# Magnetic_Encoder.net
KiCad netlist of a schematic drawn in Altium Designer
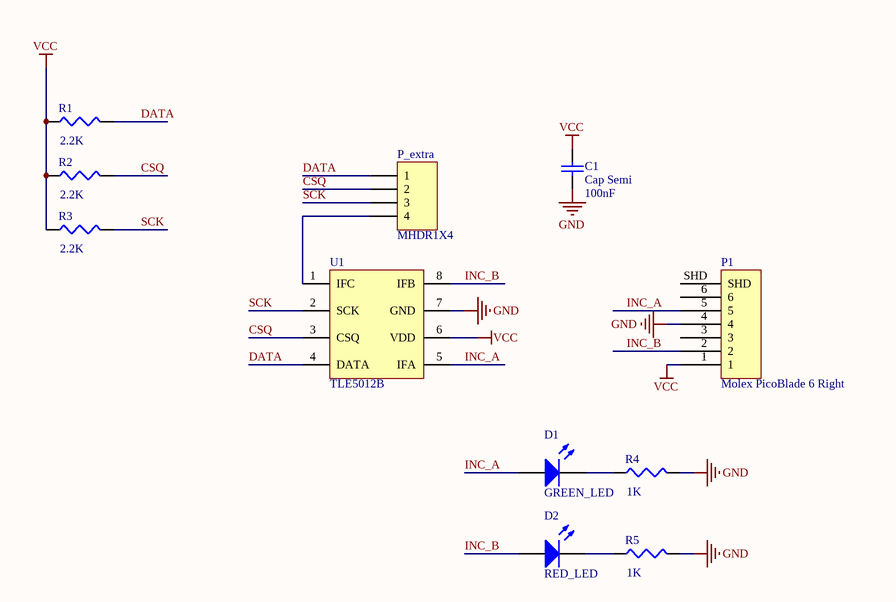
[diagram p0: Magnetic_Encoder.SchDoc]

(export (version "E")
  (design (tool "Eeschema 10.0.6"))
  (components
    (comp (ref "C1")
      (value "Cap Semi")
      (footprint "1608[0603]")
      (description "Capacitor (Semiconductor SIM Model)")
      (fields (field (name "ALTIUM_VALUE") "100nF") (field (name "PUBLISHER") "Altium Limited"))
      (libsource (lib "Miscellaneous Devices") (part "Cap Semi"))
    )
    (comp (ref "D1")
      (value "GREEN_LED")
      (footprint "1608[0603]")
      (description "Typical RED, GREEN, YELLOW, AMBER GaAs LED")
      (fields (field (name "PUBLISHER") "Altium Limited"))
      (libsource (lib "Miscellaneous Devices") (part "LED2"))
    )
    (comp (ref "D2")
      (value "RED_LED")
      (footprint "1608[0603]")
      (description "Typical RED, GREEN, YELLOW, AMBER GaAs LED")
      (fields (field (name "PUBLISHER") "Altium Limited"))
      (libsource (lib "Miscellaneous Devices") (part "LED2"))
    )
    (comp (ref "P1")
      (value "Molex PicoBlade 6 Right")
      (footprint "Molex PicoBlade 6 Right SMD")
      (libsource (lib "ImmPCB2") (part "Molex PicoBlade 6 Right"))
    )
    (comp (ref "P_extra")
      (value "MHDR1X4")
      (footprint "MHDR1X4")
      (description "Header, 4-Pin")
      (fields (field (name "PUBLISHER") "Altium Limited"))
      (libsource (lib "Miscellaneous Connectors") (part "MHDR1X4"))
    )
    (comp (ref "R1")
      (value "2.2K")
      (footprint "J1-0603")
      (description "Resistor")
      (fields (field (name "Comment") "Res3") (field (name "PUBLISHER") "Altium Limited"))
      (libsource (lib "Miscellaneous Devices") (part "Res3"))
    )
    (comp (ref "R2")
      (value "2.2K")
      (footprint "J1-0603")
      (description "Resistor")
      (fields (field (name "Comment") "Res3") (field (name "PUBLISHER") "Altium Limited"))
      (libsource (lib "Miscellaneous Devices") (part "Res3"))
    )
    (comp (ref "R3")
      (value "2.2K")
      (footprint "J1-0603")
      (description "Resistor")
      (fields (field (name "Comment") "Res3") (field (name "PUBLISHER") "Altium Limited"))
      (libsource (lib "Miscellaneous Devices") (part "Res3"))
    )
    (comp (ref "R4")
      (value "1K")
      (footprint "J1-0603")
      (description "Resistor")
      (fields (field (name "Comment") "Res3") (field (name "PUBLISHER") "Altium Limited"))
      (libsource (lib "Miscellaneous Devices") (part "Res3"))
    )
    (comp (ref "R5")
      (value "1K")
      (footprint "J1-0603")
      (description "Resistor")
      (fields (field (name "Comment") "Res3") (field (name "PUBLISHER") "Altium Limited"))
      (libsource (lib "Miscellaneous Devices") (part "Res3"))
    )
    (comp (ref "U1")
      (value "TLE5012B")
      (footprint "SO-8")
      (description "TLE5012BE1000XUMA1")
      (libsource (lib "MagneticEncoder") (part "TLE5012B"))
    )
  )
  (nets
    (net (code "1") (name "/CSQ") (class "Default")
      (node (ref "P_extra") (pin "2") (pinfunction "2_2") (pintype "passive"))
      (node (ref "R2") (pin "2") (pinfunction "2_2") (pintype "passive"))
      (node (ref "U1") (pin "3") (pinfunction "CSQ_3") (pintype "passive"))
    )
    (net (code "2") (name "/DATA") (class "Default")
      (node (ref "P_extra") (pin "1") (pinfunction "1_1") (pintype "passive"))
      (node (ref "R1") (pin "2") (pinfunction "2_2") (pintype "passive"))
      (node (ref "U1") (pin "4") (pinfunction "DATA_4") (pintype "passive"))
    )
    (net (code "3") (name "/INC_A") (class "Default")
      (node (ref "D1") (pin "1") (pinfunction "A_1") (pintype "passive"))
      (node (ref "P1") (pin "5") (pinfunction "5_5") (pintype "passive"))
      (node (ref "U1") (pin "5") (pinfunction "IFA_5") (pintype "passive"))
    )
    (net (code "4") (name "/INC_B") (class "Default")
      (node (ref "D2") (pin "1") (pinfunction "A_1") (pintype "passive"))
      (node (ref "P1") (pin "2") (pinfunction "2_2") (pintype "passive"))
      (node (ref "U1") (pin "8") (pinfunction "IFB_8") (pintype "passive"))
    )
    (net (code "5") (name "/SCK") (class "Default")
      (node (ref "P_extra") (pin "3") (pinfunction "3_3") (pintype "passive"))
      (node (ref "R3") (pin "2") (pinfunction "2_2") (pintype "passive"))
      (node (ref "U1") (pin "2") (pinfunction "SCK_2") (pintype "passive"))
    )
    (net (code "6") (name "GND") (class "Default")
      (node (ref "C1") (pin "1") (pinfunction "1_1") (pintype "passive"))
      (node (ref "P1") (pin "4") (pinfunction "4_4") (pintype "passive"))
      (node (ref "R4") (pin "2") (pinfunction "2_2") (pintype "passive"))
      (node (ref "R5") (pin "2") (pinfunction "2_2") (pintype "passive"))
      (node (ref "U1") (pin "7") (pinfunction "GND_7") (pintype "passive"))
    )
    (net (code "7") (name "Net-(D1-K)") (class "Default")
      (node (ref "D1") (pin "2") (pinfunction "K_2") (pintype "passive"))
      (node (ref "R4") (pin "1") (pinfunction "1_1") (pintype "passive"))
    )
    (net (code "8") (name "Net-(D2-K)") (class "Default")
      (node (ref "D2") (pin "2") (pinfunction "K_2") (pintype "passive"))
      (node (ref "R5") (pin "1") (pinfunction "1_1") (pintype "passive"))
    )
    (net (code "9") (name "Net-(U1-IFC)") (class "Default")
      (node (ref "P_extra") (pin "4") (pinfunction "4_4") (pintype "passive"))
      (node (ref "U1") (pin "1") (pinfunction "IFC_1") (pintype "passive"))
    )
    (net (code "10") (name "VCC") (class "Default")
      (node (ref "C1") (pin "2") (pinfunction "2_2") (pintype "passive"))
      (node (ref "P1") (pin "1") (pinfunction "1_1") (pintype "passive"))
      (node (ref "R1") (pin "1") (pinfunction "1_1") (pintype "passive"))
      (node (ref "R2") (pin "1") (pinfunction "1_1") (pintype "passive"))
      (node (ref "R3") (pin "1") (pinfunction "1_1") (pintype "passive"))
      (node (ref "U1") (pin "6") (pinfunction "VDD_6") (pintype "passive"))
    )
    (net (code "11") (name "unconnected-(P1-Pad3)") (class "Default")
      (node (ref "P1") (pin "3") (pinfunction "3_3") (pintype "passive"))
    )
    (net (code "12") (name "unconnected-(P1-Pad6)") (class "Default")
      (node (ref "P1") (pin "6") (pinfunction "6_6") (pintype "passive"))
    )
    (net (code "13") (name "unconnected-(P1-PadSHD)") (class "Default")
      (node (ref "P1") (pin "SHD") (pinfunction "SHD_SHD") (pintype "passive"))
    )
  )
)
